# 02_-Thermistors.net
KiCad netlist of a schematic drawn in Altium Designer
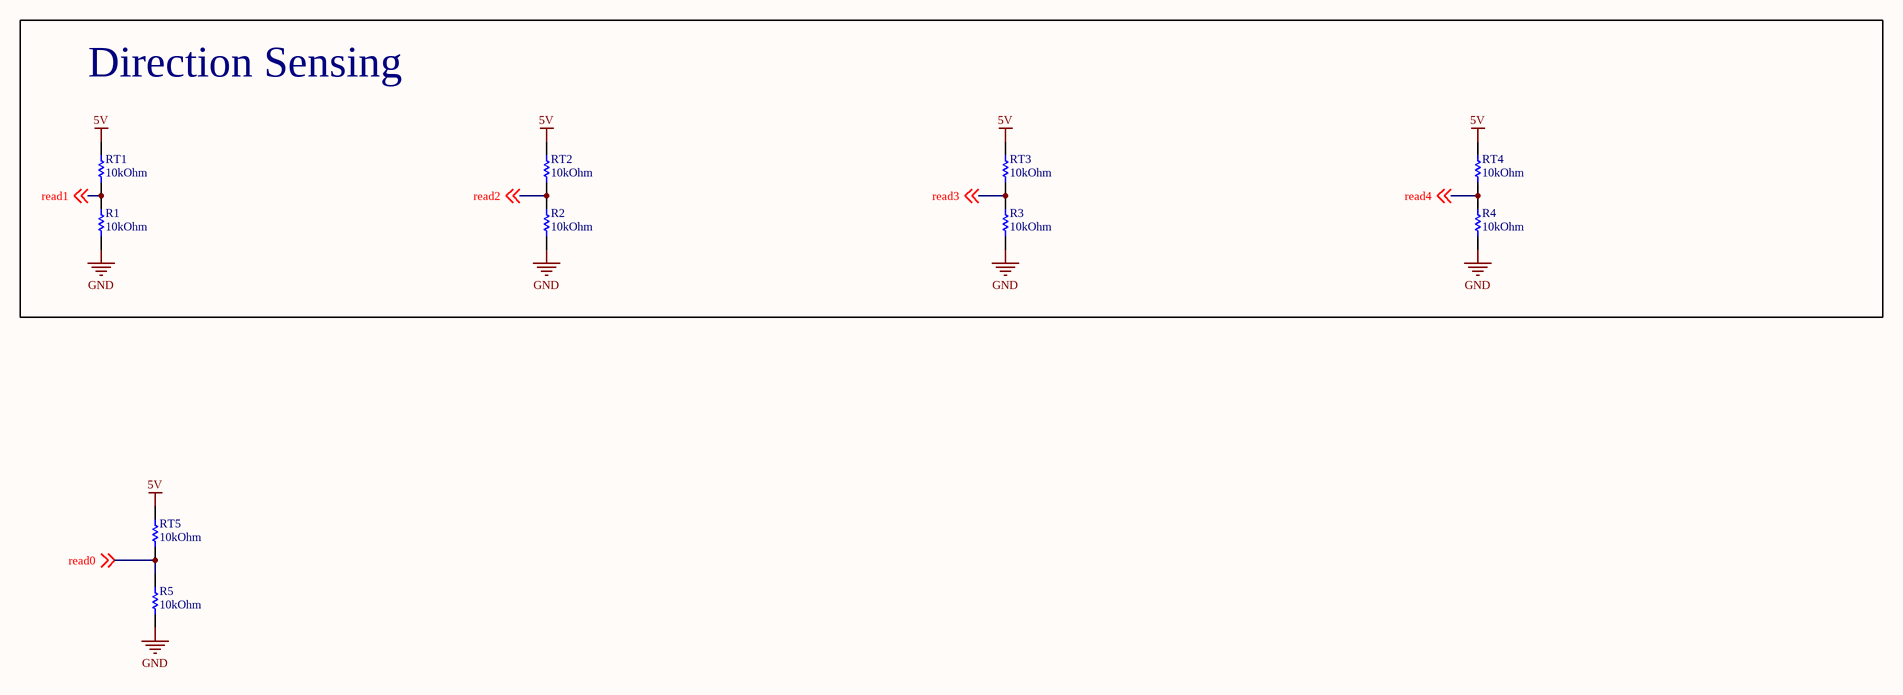
[diagram p0: [02]-Thermistors.SchDoc]

(export (version "E")
  (design (tool "Eeschema 10.0.6"))
  (components
    (comp (ref "R1")
      (value "10kOhm")
      (footprint "RESC2013X60X35LL10T20")
      (description "RES 10.0K OHM 1/8W 1% 0805 SMD")
      (fields (field (name "MPN") "RC0805FR-0710KL") (field (name "MANUFACTURER") "Yageo"))
      (libsource (lib "Altium Content Vault") (part "RES-2"))
    )
    (comp (ref "R2")
      (value "10kOhm")
      (footprint "RESC2013X60X35LL10T20")
      (description "RES 10.0K OHM 1/8W 1% 0805 SMD")
      (fields (field (name "MPN") "RC0805FR-0710KL") (field (name "MANUFACTURER") "Yageo"))
      (libsource (lib "Altium Content Vault") (part "RES-2"))
    )
    (comp (ref "R3")
      (value "10kOhm")
      (footprint "RESC2013X60X35LL10T20")
      (description "RES 10.0K OHM 1/8W 1% 0805 SMD")
      (fields (field (name "MPN") "RC0805FR-0710KL") (field (name "MANUFACTURER") "Yageo"))
      (libsource (lib "Altium Content Vault") (part "RES-2"))
    )
    (comp (ref "R4")
      (value "10kOhm")
      (footprint "RESC2013X60X35LL10T20")
      (description "RES 10.0K OHM 1/8W 1% 0805 SMD")
      (fields (field (name "MPN") "RC0805FR-0710KL") (field (name "MANUFACTURER") "Yageo"))
      (libsource (lib "Altium Content Vault") (part "RES-2"))
    )
    (comp (ref "R5")
      (value "10kOhm")
      (footprint "RESC2013X60X35LL10T20")
      (description "RES 10.0K OHM 1/8W 1% 0805 SMD")
      (fields (field (name "MPN") "RC0805FR-0710KL") (field (name "MANUFACTURER") "Yageo"))
      (libsource (lib "Altium Content Vault") (part "RES-2"))
    )
    (comp (ref "RT1")
      (value "10kOhm")
      (footprint "RESC2013X100X45NL20T25")
      (description "Chip Thermistor, 10 KOhm, +/- 5%, 200 mW, -40 to 125 degC, 0805 (2012 Metric), RoHS, Tape and Reel")
      (fields (field (name "MANUFACTURER") "Murata") (field (name "MPN") "NTCS0805E3103FLT"))
      (libsource (lib "Altium Content Vault") (part "RES-THERMAL-2"))
    )
    (comp (ref "RT2")
      (value "10kOhm")
      (footprint "RESC2013X100X45NL20T25")
      (description "Chip Thermistor, 10 KOhm, +/- 5%, 200 mW, -40 to 125 degC, 0805 (2012 Metric), RoHS, Tape and Reel")
      (fields (field (name "MANUFACTURER") "Murata") (field (name "MPN") "NTCS0805E3103FLT"))
      (libsource (lib "Altium Content Vault") (part "RES-THERMAL-2"))
    )
    (comp (ref "RT3")
      (value "10kOhm")
      (footprint "RESC2013X100X45NL20T25")
      (description "Chip Thermistor, 10 KOhm, +/- 5%, 200 mW, -40 to 125 degC, 0805 (2012 Metric), RoHS, Tape and Reel")
      (fields (field (name "MANUFACTURER") "Murata") (field (name "MPN") "NTCS0805E3103FLT"))
      (libsource (lib "Altium Content Vault") (part "RES-THERMAL-2"))
    )
    (comp (ref "RT4")
      (value "10kOhm")
      (footprint "RESC2013X100X45NL20T25")
      (description "Chip Thermistor, 10 KOhm, +/- 5%, 200 mW, -40 to 125 degC, 0805 (2012 Metric), RoHS, Tape and Reel")
      (fields (field (name "MANUFACTURER") "Murata") (field (name "MPN") "NTCS0805E3103FLT"))
      (libsource (lib "Altium Content Vault") (part "RES-THERMAL-2"))
    )
    (comp (ref "RT5")
      (value "10kOhm")
      (footprint "RESC2013X100X45NL20T25")
      (description "Chip Thermistor, 10 KOhm, +/- 5%, 200 mW, -40 to 125 degC, 0805 (2012 Metric), RoHS, Tape and Reel")
      (fields (field (name "MANUFACTURER") "Murata") (field (name "MPN") "NTCS0805E3103FLT"))
      (libsource (lib "Altium Content Vault") (part "RES-THERMAL-2"))
    )
  )
  (nets
    (net (code "1") (name "5V") (class "Default")
      (node (ref "RT1") (pin "2") (pinfunction "2_2") (pintype "passive"))
      (node (ref "RT2") (pin "2") (pinfunction "2_2") (pintype "passive"))
      (node (ref "RT3") (pin "2") (pinfunction "2_2") (pintype "passive"))
      (node (ref "RT4") (pin "2") (pinfunction "2_2") (pintype "passive"))
      (node (ref "RT5") (pin "2") (pinfunction "2_2") (pintype "passive"))
    )
    (net (code "2") (name "GND") (class "Default")
      (node (ref "R1") (pin "1") (pinfunction "1_1") (pintype "passive"))
      (node (ref "R2") (pin "1") (pinfunction "1_1") (pintype "passive"))
      (node (ref "R3") (pin "1") (pinfunction "1_1") (pintype "passive"))
      (node (ref "R4") (pin "1") (pinfunction "1_1") (pintype "passive"))
      (node (ref "R5") (pin "1") (pinfunction "1_1") (pintype "passive"))
    )
    (net (code "3") (name "read0") (class "Default")
      (node (ref "R5") (pin "2") (pinfunction "2_2") (pintype "passive"))
      (node (ref "RT5") (pin "1") (pinfunction "1_1") (pintype "passive"))
    )
    (net (code "4") (name "read1") (class "Default")
      (node (ref "R1") (pin "2") (pinfunction "2_2") (pintype "passive"))
      (node (ref "RT1") (pin "1") (pinfunction "1_1") (pintype "passive"))
    )
    (net (code "5") (name "read2") (class "Default")
      (node (ref "R2") (pin "2") (pinfunction "2_2") (pintype "passive"))
      (node (ref "RT2") (pin "1") (pinfunction "1_1") (pintype "passive"))
    )
    (net (code "6") (name "read3") (class "Default")
      (node (ref "R3") (pin "2") (pinfunction "2_2") (pintype "passive"))
      (node (ref "RT3") (pin "1") (pinfunction "1_1") (pintype "passive"))
    )
    (net (code "7") (name "read4") (class "Default")
      (node (ref "R4") (pin "2") (pinfunction "2_2") (pintype "passive"))
      (node (ref "RT4") (pin "1") (pinfunction "1_1") (pintype "passive"))
    )
  )
)
